# schematicv2.net
KiCad netlist of a schematic drawn in EAGLE
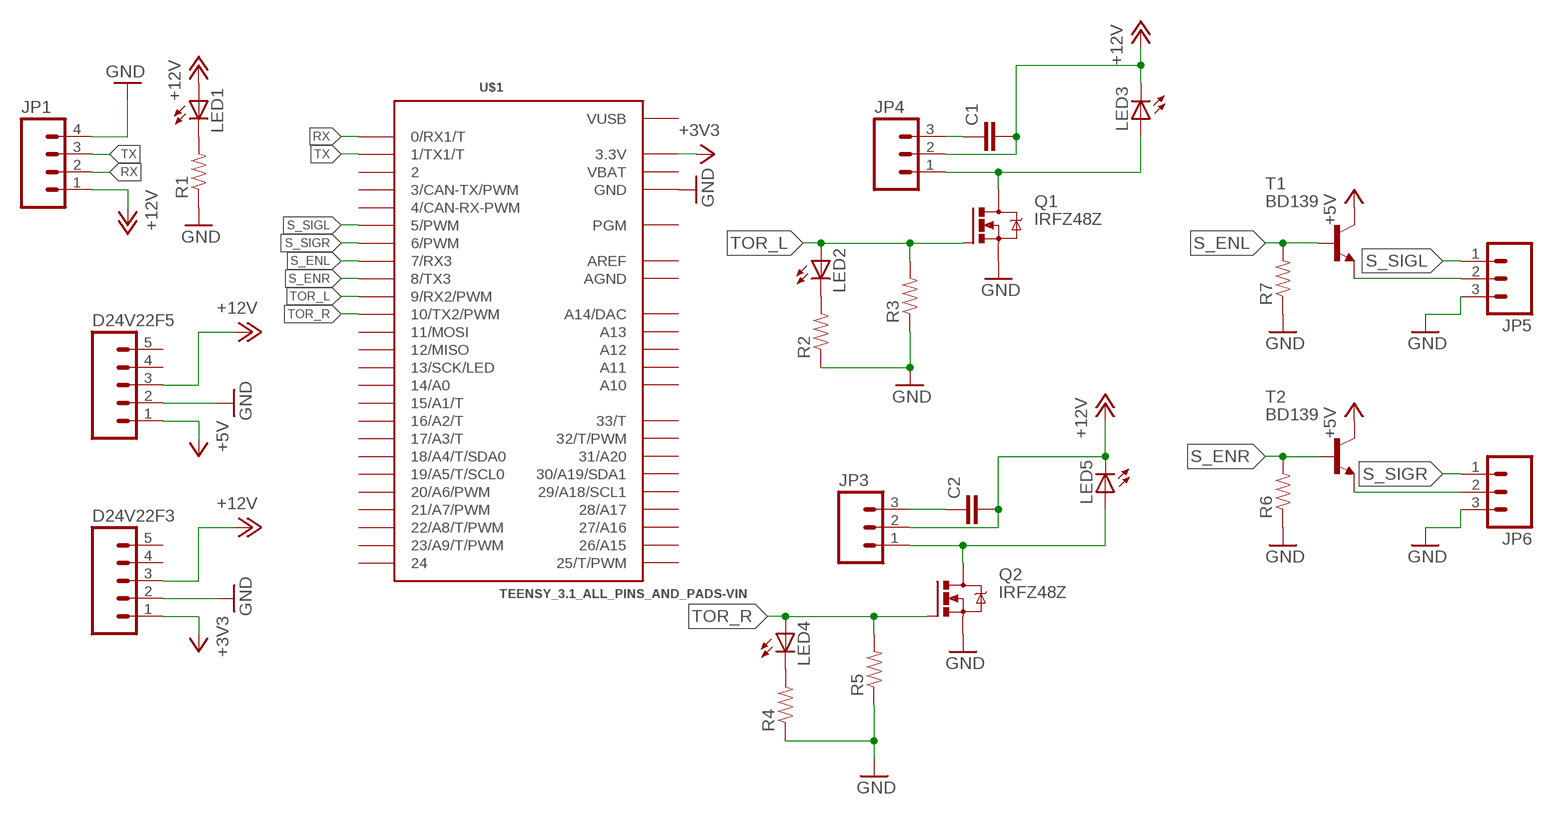
[diagram p0: schematic, sheet 1]

(export (version "E")
  (design (tool "Eeschema 10.0.6"))
  (components
    (comp (ref "C1")
      (value "CAP0805")
      (footprint "eagle-import:0805")
      (libsource (lib "eagle-import") (part "CAP0805"))
    )
    (comp (ref "C2")
      (value "CAP0805")
      (footprint "eagle-import:0805")
      (libsource (lib "eagle-import") (part "CAP0805"))
    )
    (comp (ref "D24V22F3")
      (value "M05PTH")
      (footprint "eagle-import:1X05")
      (libsource (lib "eagle-import") (part "M05PTH"))
    )
    (comp (ref "D24V22F5")
      (value "M05PTH")
      (footprint "eagle-import:1X05")
      (libsource (lib "eagle-import") (part "M05PTH"))
    )
    (comp (ref "JP1")
      (value "M04POLAR")
      (footprint "eagle-import:MOLEX-1X4")
      (libsource (lib "eagle-import") (part "M04POLAR"))
    )
    (comp (ref "JP3")
      (value "M03POLAR")
      (footprint "eagle-import:MOLEX-1X3")
      (libsource (lib "eagle-import") (part "M03POLAR"))
    )
    (comp (ref "JP4")
      (value "M03POLAR")
      (footprint "eagle-import:MOLEX-1X3")
      (libsource (lib "eagle-import") (part "M03POLAR"))
    )
    (comp (ref "JP5")
      (value "M03POLAR")
      (footprint "eagle-import:MOLEX-1X3")
      (libsource (lib "eagle-import") (part "M03POLAR"))
    )
    (comp (ref "JP6")
      (value "M03POLAR")
      (footprint "eagle-import:MOLEX-1X3")
      (libsource (lib "eagle-import") (part "M03POLAR"))
    )
    (comp (ref "LED1")
      (value "LEDCHIP-LED0603")
      (footprint "eagle-import:CHIP-LED0603")
      (libsource (lib "eagle-import") (part "LEDCHIP-LED0603"))
    )
    (comp (ref "LED2")
      (value "LEDCHIP-LED0603")
      (footprint "eagle-import:CHIP-LED0603")
      (libsource (lib "eagle-import") (part "LEDCHIP-LED0603"))
    )
    (comp (ref "LED3")
      (value "LEDCHIP-LED0603")
      (footprint "eagle-import:CHIP-LED0603")
      (libsource (lib "eagle-import") (part "LEDCHIP-LED0603"))
    )
    (comp (ref "LED4")
      (value "LEDCHIP-LED0603")
      (footprint "eagle-import:CHIP-LED0603")
      (libsource (lib "eagle-import") (part "LEDCHIP-LED0603"))
    )
    (comp (ref "LED5")
      (value "LEDCHIP-LED0603")
      (footprint "eagle-import:CHIP-LED0603")
      (libsource (lib "eagle-import") (part "LEDCHIP-LED0603"))
    )
    (comp (ref "Q1")
      (value "IRFZ48Z")
      (footprint "eagle-import:TO220BH")
      (libsource (lib "eagle-import") (part "IRFZ48Z"))
    )
    (comp (ref "Q2")
      (value "IRFZ48Z")
      (footprint "eagle-import:TO220BH")
      (libsource (lib "eagle-import") (part "IRFZ48Z"))
    )
    (comp (ref "R1")
      (value "RESISTOR0805-RES")
      (footprint "eagle-import:0805")
      (libsource (lib "eagle-import") (part "RESISTOR0805-RES"))
    )
    (comp (ref "R2")
      (value "RESISTOR0805-RES")
      (footprint "eagle-import:0805")
      (libsource (lib "eagle-import") (part "RESISTOR0805-RES"))
    )
    (comp (ref "R3")
      (value "RESISTOR0805-RES")
      (footprint "eagle-import:0805")
      (libsource (lib "eagle-import") (part "RESISTOR0805-RES"))
    )
    (comp (ref "R4")
      (value "RESISTOR0805-RES")
      (footprint "eagle-import:0805")
      (libsource (lib "eagle-import") (part "RESISTOR0805-RES"))
    )
    (comp (ref "R5")
      (value "RESISTOR0805-RES")
      (footprint "eagle-import:0805")
      (libsource (lib "eagle-import") (part "RESISTOR0805-RES"))
    )
    (comp (ref "R6")
      (value "RESISTOR0805-RES")
      (footprint "eagle-import:0805")
      (libsource (lib "eagle-import") (part "RESISTOR0805-RES"))
    )
    (comp (ref "R7")
      (value "RESISTOR0805-RES")
      (footprint "eagle-import:0805")
      (libsource (lib "eagle-import") (part "RESISTOR0805-RES"))
    )
    (comp (ref "T1")
      (value "BD139")
      (footprint "eagle-import:TO126")
      (libsource (lib "eagle-import") (part "BD139"))
    )
    (comp (ref "T2")
      (value "BD139")
      (footprint "eagle-import:TO126")
      (libsource (lib "eagle-import") (part "BD139"))
    )
    (comp (ref "U$1")
      (value "TEENSY_3.1_ALL_PINS_AND_PADS-VIN")
      (footprint "eagle-import:TEENSY_3.1_ALLPINS-VIN")
      (libsource (lib "eagle-import") (part "TEENSY_3.1_ALL_PINS_AND_PADS-VIN"))
    )
  )
  (nets
    (net (code "1") (name "+3V3") (class "Default")
      (node (ref "D24V22F3") (pin "1") (pinfunction "1_1") (pintype "passive"))
      (node (ref "U$1") (pin "3.3V") (pinfunction "3.3V_3.3V") (pintype "power_in"))
      (node (ref "U$1") (pin "3.3V1") (pinfunction "3.3V_3.3V1") (pintype "power_in"))
      (node (ref "U$1") (pin "3.3V2") (pinfunction "3.3V_3.3V2") (pintype "power_in"))
    )
    (net (code "2") (name "+5V") (class "Default")
      (node (ref "D24V22F5") (pin "1") (pinfunction "1_1") (pintype "passive"))
      (node (ref "T1") (pin "2") (pinfunction "C_2") (pintype "passive"))
      (node (ref "T2") (pin "2") (pinfunction "C_2") (pintype "passive"))
    )
    (net (code "3") (name "+12V") (class "Default")
      (node (ref "C1") (pin "2") (pinfunction "2_2") (pintype "passive"))
      (node (ref "C2") (pin "2") (pinfunction "2_2") (pintype "passive"))
      (node (ref "D24V22F3") (pin "3") (pinfunction "3_3") (pintype "passive"))
      (node (ref "D24V22F5") (pin "3") (pinfunction "3_3") (pintype "passive"))
      (node (ref "JP1") (pin "1") (pinfunction "1_1") (pintype "passive"))
      (node (ref "JP3") (pin "2") (pinfunction "2_2") (pintype "passive"))
      (node (ref "JP4") (pin "2") (pinfunction "2_2") (pintype "passive"))
      (node (ref "LED1") (pin "A") (pinfunction "A_A") (pintype "passive"))
      (node (ref "LED3") (pin "C") (pinfunction "C_C") (pintype "passive"))
      (node (ref "LED5") (pin "C") (pinfunction "C_C") (pintype "passive"))
    )
    (net (code "4") (name "/AGND") (class "Default")
      (node (ref "U$1") (pin "AGND") (pinfunction "AGND_AGND") (pintype "power_in"))
    )
    (net (code "5") (name "/AREF") (class "Default")
      (node (ref "U$1") (pin "AREF") (pinfunction "AREF_AREF") (pintype "power_in"))
    )
    (net (code "6") (name "/VBAT") (class "Default")
      (node (ref "U$1") (pin "VBAT") (pinfunction "VBAT_VBAT") (pintype "power_in"))
    )
    (net (code "7") (name "/VUSB") (class "Default")
      (node (ref "U$1") (pin "VUSB") (pinfunction "VUSB_VUSB") (pintype "power_in"))
    )
    (net (code "8") (name "GND") (class "Default")
      (node (ref "D24V22F3") (pin "2") (pinfunction "2_2") (pintype "passive"))
      (node (ref "D24V22F5") (pin "2") (pinfunction "2_2") (pintype "passive"))
      (node (ref "JP1") (pin "4") (pinfunction "4_4") (pintype "passive"))
      (node (ref "JP5") (pin "3") (pinfunction "3_3") (pintype "passive"))
      (node (ref "JP6") (pin "3") (pinfunction "3_3") (pintype "passive"))
      (node (ref "Q1") (pin "S") (pinfunction "S_S") (pintype "passive"))
      (node (ref "Q2") (pin "S") (pinfunction "S_S") (pintype "passive"))
      (node (ref "R1") (pin "1") (pinfunction "1_1") (pintype "passive"))
      (node (ref "R2") (pin "1") (pinfunction "1_1") (pintype "passive"))
      (node (ref "R3") (pin "1") (pinfunction "1_1") (pintype "passive"))
      (node (ref "R4") (pin "1") (pinfunction "1_1") (pintype "passive"))
      (node (ref "R5") (pin "1") (pinfunction "1_1") (pintype "passive"))
      (node (ref "R6") (pin "1") (pinfunction "1_1") (pintype "passive"))
      (node (ref "R7") (pin "1") (pinfunction "1_1") (pintype "passive"))
      (node (ref "U$1") (pin "GND") (pinfunction "GND_GND") (pintype "power_in"))
      (node (ref "U$1") (pin "GND1") (pinfunction "GND_GND1") (pintype "power_in"))
      (node (ref "U$1") (pin "GND2") (pinfunction "GND_GND2") (pintype "power_in"))
    )
    (net (code "9") (name "Net-(C1-Pad1)") (class "Default")
      (node (ref "C1") (pin "1") (pinfunction "1_1") (pintype "passive"))
      (node (ref "JP4") (pin "3") (pinfunction "3_3") (pintype "passive"))
    )
    (net (code "10") (name "Net-(C2-Pad1)") (class "Default")
      (node (ref "C2") (pin "1") (pinfunction "1_1") (pintype "passive"))
      (node (ref "JP3") (pin "3") (pinfunction "3_3") (pintype "passive"))
    )
    (net (code "11") (name "Net-(JP3-Pad1)") (class "Default")
      (node (ref "JP3") (pin "1") (pinfunction "1_1") (pintype "passive"))
      (node (ref "LED5") (pin "A") (pinfunction "A_A") (pintype "passive"))
      (node (ref "Q2") (pin "D") (pinfunction "D_D") (pintype "passive"))
    )
    (net (code "12") (name "Net-(JP4-Pad1)") (class "Default")
      (node (ref "JP4") (pin "1") (pinfunction "1_1") (pintype "passive"))
      (node (ref "LED3") (pin "A") (pinfunction "A_A") (pintype "passive"))
      (node (ref "Q1") (pin "D") (pinfunction "D_D") (pintype "passive"))
    )
    (net (code "13") (name "Net-(LED1-PadC)") (class "Default")
      (node (ref "LED1") (pin "C") (pinfunction "C_C") (pintype "passive"))
      (node (ref "R1") (pin "2") (pinfunction "2_2") (pintype "passive"))
    )
    (net (code "14") (name "Net-(LED2-PadC)") (class "Default")
      (node (ref "LED2") (pin "C") (pinfunction "C_C") (pintype "passive"))
      (node (ref "R2") (pin "2") (pinfunction "2_2") (pintype "passive"))
    )
    (net (code "15") (name "Net-(LED4-PadC)") (class "Default")
      (node (ref "LED4") (pin "C") (pinfunction "C_C") (pintype "passive"))
      (node (ref "R4") (pin "2") (pinfunction "2_2") (pintype "passive"))
    )
    (net (code "16") (name "Net-(T1-E)") (class "Default")
      (node (ref "JP5") (pin "2") (pinfunction "2_2") (pintype "passive"))
      (node (ref "T1") (pin "1") (pinfunction "E_1") (pintype "passive"))
    )
    (net (code "17") (name "Net-(T2-E)") (class "Default")
      (node (ref "JP6") (pin "2") (pinfunction "2_2") (pintype "passive"))
      (node (ref "T2") (pin "1") (pinfunction "E_1") (pintype "passive"))
    )
    (net (code "18") (name "RX") (class "Default")
      (node (ref "JP1") (pin "2") (pinfunction "2_2") (pintype "passive"))
      (node (ref "U$1") (pin "0") (pinfunction "0/RX1/T_0") (pintype "bidirectional"))
    )
    (net (code "19") (name "S_ENL") (class "Default")
      (node (ref "R7") (pin "2") (pinfunction "2_2") (pintype "passive"))
      (node (ref "T1") (pin "3") (pinfunction "B_3") (pintype "passive"))
      (node (ref "U$1") (pin "7") (pinfunction "7/RX3_7") (pintype "bidirectional"))
    )
    (net (code "20") (name "S_ENR") (class "Default")
      (node (ref "R6") (pin "2") (pinfunction "2_2") (pintype "passive"))
      (node (ref "T2") (pin "3") (pinfunction "B_3") (pintype "passive"))
      (node (ref "U$1") (pin "8") (pinfunction "8/TX3_8") (pintype "bidirectional"))
    )
    (net (code "21") (name "S_SIGL") (class "Default")
      (node (ref "JP5") (pin "1") (pinfunction "1_1") (pintype "passive"))
      (node (ref "U$1") (pin "5") (pinfunction "5/PWM_5") (pintype "bidirectional"))
    )
    (net (code "22") (name "S_SIGR") (class "Default")
      (node (ref "JP6") (pin "1") (pinfunction "1_1") (pintype "passive"))
      (node (ref "U$1") (pin "6") (pinfunction "6/PWM_6") (pintype "bidirectional"))
    )
    (net (code "23") (name "TOR_L") (class "Default")
      (node (ref "LED2") (pin "A") (pinfunction "A_A") (pintype "passive"))
      (node (ref "Q1") (pin "G") (pinfunction "G_G") (pintype "passive"))
      (node (ref "R3") (pin "2") (pinfunction "2_2") (pintype "passive"))
      (node (ref "U$1") (pin "9") (pinfunction "9/RX2/PWM_9") (pintype "bidirectional"))
    )
    (net (code "24") (name "TOR_R") (class "Default")
      (node (ref "LED4") (pin "A") (pinfunction "A_A") (pintype "passive"))
      (node (ref "Q2") (pin "G") (pinfunction "G_G") (pintype "passive"))
      (node (ref "R5") (pin "2") (pinfunction "2_2") (pintype "passive"))
      (node (ref "U$1") (pin "10") (pinfunction "10/TX2/PWM_10") (pintype "bidirectional"))
    )
    (net (code "25") (name "TX") (class "Default")
      (node (ref "JP1") (pin "3") (pinfunction "3_3") (pintype "passive"))
      (node (ref "U$1") (pin "1") (pinfunction "1/TX1/T_1") (pintype "bidirectional"))
    )
    (net (code "26") (name "unconnected-(D24V22F3-Pad4)") (class "Default")
      (node (ref "D24V22F3") (pin "4") (pinfunction "4_4") (pintype "passive"))
    )
    (net (code "27") (name "unconnected-(D24V22F3-Pad5)") (class "Default")
      (node (ref "D24V22F3") (pin "5") (pinfunction "5_5") (pintype "passive"))
    )
    (net (code "28") (name "unconnected-(D24V22F5-Pad4)") (class "Default")
      (node (ref "D24V22F5") (pin "4") (pinfunction "4_4") (pintype "passive"))
    )
    (net (code "29") (name "unconnected-(D24V22F5-Pad5)") (class "Default")
      (node (ref "D24V22F5") (pin "5") (pinfunction "5_5") (pintype "passive"))
    )
    (net (code "30") (name "unconnected-(U$1-3{slash}CAN-TX{slash}PWM-Pad3)") (class "Default")
      (node (ref "U$1") (pin "3") (pinfunction "3/CAN-TX/PWM_3") (pintype "bidirectional"))
    )
    (net (code "31") (name "unconnected-(U$1-4{slash}CAN-RX-PWM-Pad4)") (class "Default")
      (node (ref "U$1") (pin "4") (pinfunction "4/CAN-RX-PWM_4") (pintype "bidirectional"))
    )
    (net (code "32") (name "unconnected-(U$1-11{slash}MOSI-Pad11)") (class "Default")
      (node (ref "U$1") (pin "11") (pinfunction "11/MOSI_11") (pintype "bidirectional"))
    )
    (net (code "33") (name "unconnected-(U$1-12{slash}MISO-Pad12)") (class "Default")
      (node (ref "U$1") (pin "12") (pinfunction "12/MISO_12") (pintype "bidirectional"))
    )
    (net (code "34") (name "unconnected-(U$1-13{slash}SCK{slash}LED-Pad13)") (class "Default")
      (node (ref "U$1") (pin "13") (pinfunction "13/SCK/LED_13") (pintype "bidirectional"))
    )
    (net (code "35") (name "unconnected-(U$1-15{slash}A1{slash}T-Pad15{slash}A1)") (class "Default")
      (node (ref "U$1") (pin "15/A1") (pinfunction "15/A1/T_15/A1") (pintype "bidirectional"))
    )
    (net (code "36") (name "unconnected-(U$1-16{slash}A2{slash}T-Pad16{slash}A2)") (class "Default")
      (node (ref "U$1") (pin "16/A2") (pinfunction "16/A2/T_16/A2") (pintype "bidirectional"))
    )
    (net (code "37") (name "unconnected-(U$1-17{slash}A3{slash}T-Pad17{slash}A3)") (class "Default")
      (node (ref "U$1") (pin "17/A3") (pinfunction "17/A3/T_17/A3") (pintype "bidirectional"))
    )
    (net (code "38") (name "unconnected-(U$1-18{slash}A4{slash}T{slash}SDA0-Pad18{slash}A4)") (class "Default")
      (node (ref "U$1") (pin "18/A4") (pinfunction "18/A4/T/SDA0_18/A4") (pintype "bidirectional"))
    )
    (net (code "39") (name "unconnected-(U$1-19{slash}A5{slash}T{slash}SCL0-Pad19{slash}A5)") (class "Default")
      (node (ref "U$1") (pin "19/A5") (pinfunction "19/A5/T/SCL0_19/A5") (pintype "bidirectional"))
    )
    (net (code "40") (name "unconnected-(U$1-20{slash}A6{slash}PWM-Pad20{slash}A6)") (class "Default")
      (node (ref "U$1") (pin "20/A6") (pinfunction "20/A6/PWM_20/A6") (pintype "bidirectional"))
    )
    (net (code "41") (name "unconnected-(U$1-21{slash}A7{slash}PWM-Pad21{slash}A7)") (class "Default")
      (node (ref "U$1") (pin "21/A7") (pinfunction "21/A7/PWM_21/A7") (pintype "bidirectional"))
    )
    (net (code "42") (name "unconnected-(U$1-22{slash}A8{slash}T{slash}PWM-Pad22{slash}A8)") (class "Default")
      (node (ref "U$1") (pin "22/A8") (pinfunction "22/A8/T/PWM_22/A8") (pintype "bidirectional"))
    )
    (net (code "43") (name "unconnected-(U$1-23{slash}A9{slash}T{slash}PWM-Pad23{slash}A9)") (class "Default")
      (node (ref "U$1") (pin "23/A9") (pinfunction "23/A9/T/PWM_23/A9") (pintype "bidirectional"))
    )
    (net (code "44") (name "unconnected-(U$1-25{slash}T{slash}PWM-Pad25)") (class "Default")
      (node (ref "U$1") (pin "25") (pinfunction "25/T/PWM_25") (pintype "bidirectional"))
    )
    (net (code "45") (name "unconnected-(U$1-26{slash}A15-Pad26)") (class "Default")
      (node (ref "U$1") (pin "26") (pinfunction "26/A15_26") (pintype "bidirectional"))
    )
    (net (code "46") (name "unconnected-(U$1-27{slash}A16-Pad27)") (class "Default")
      (node (ref "U$1") (pin "27") (pinfunction "27/A16_27") (pintype "bidirectional"))
    )
    (net (code "47") (name "unconnected-(U$1-28{slash}A17-Pad28)") (class "Default")
      (node (ref "U$1") (pin "28") (pinfunction "28/A17_28") (pintype "bidirectional"))
    )
    (net (code "48") (name "unconnected-(U$1-29{slash}A18{slash}SCL1-Pad29)") (class "Default")
      (node (ref "U$1") (pin "29") (pinfunction "29/A18/SCL1_29") (pintype "bidirectional"))
    )
    (net (code "49") (name "unconnected-(U$1-30{slash}A19{slash}SDA1-Pad30)") (class "Default")
      (node (ref "U$1") (pin "30") (pinfunction "30/A19/SDA1_30") (pintype "bidirectional"))
    )
    (net (code "50") (name "unconnected-(U$1-31{slash}A20-Pad31)") (class "Default")
      (node (ref "U$1") (pin "31") (pinfunction "31/A20_31") (pintype "bidirectional"))
    )
    (net (code "51") (name "unconnected-(U$1-32{slash}T{slash}PWM-Pad32)") (class "Default")
      (node (ref "U$1") (pin "32") (pinfunction "32/T/PWM_32") (pintype "bidirectional"))
    )
    (net (code "52") (name "unconnected-(U$1-33{slash}T-Pad33)") (class "Default")
      (node (ref "U$1") (pin "33") (pinfunction "33/T_33") (pintype "bidirectional"))
    )
    (net (code "53") (name "unconnected-(U$1-A14{slash}DAC-PadA14)") (class "Default")
      (node (ref "U$1") (pin "A14") (pinfunction "A14/DAC_A14") (pintype "bidirectional"))
    )
    (net (code "54") (name "unconnected-(U$1-Pad2)") (class "Default")
      (node (ref "U$1") (pin "2") (pinfunction "2_2") (pintype "bidirectional"))
    )
    (net (code "55") (name "unconnected-(U$1-Pad14{slash}A0)") (class "Default")
      (node (ref "U$1") (pin "14/A0") (pinfunction "14/A0_14/A0") (pintype "bidirectional"))
    )
    (net (code "56") (name "unconnected-(U$1-Pad24)") (class "Default")
      (node (ref "U$1") (pin "24") (pinfunction "24_24") (pintype "bidirectional"))
    )
    (net (code "57") (name "unconnected-(U$1-PadA10)") (class "Default")
      (node (ref "U$1") (pin "A10") (pinfunction "A10_A10") (pintype "bidirectional"))
    )
    (net (code "58") (name "unconnected-(U$1-PadA11)") (class "Default")
      (node (ref "U$1") (pin "A11") (pinfunction "A11_A11") (pintype "bidirectional"))
    )
    (net (code "59") (name "unconnected-(U$1-PadA12)") (class "Default")
      (node (ref "U$1") (pin "A12") (pinfunction "A12_A12") (pintype "bidirectional"))
    )
    (net (code "60") (name "unconnected-(U$1-PadA13)") (class "Default")
      (node (ref "U$1") (pin "A13") (pinfunction "A13_A13") (pintype "bidirectional"))
    )
    (net (code "61") (name "unconnected-(U$1-PadPGM)") (class "Default")
      (node (ref "U$1") (pin "PGM") (pinfunction "PGM_PGM") (pintype "bidirectional"))
    )
  )
)
